# TPCapTH.net
KiCad netlist of a schematic drawn in Altium Designer
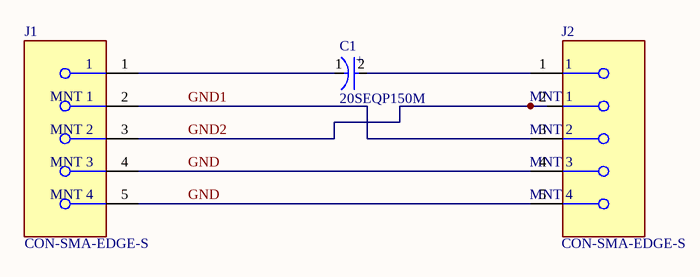
[diagram p0: TPCapTH.SchDoc]

(export (version "E")
  (design (tool "Eeschema 10.0.6"))
  (components
    (comp (ref "C1")
      (value "20SEQP150M")
      (footprint "FP-OS-CON-TH-F13-d_0_6-MFG")
      (description "Conductive Polymer Aluminum Solid Capacitors (OS-CON) 150uF ±20% 20V RADIAL TH 10x13mm")
      (fields (field (name "TOLERANCE") "20%"))
      (libsource (lib "Altium Content Vault") (part "203bc49f2ac43e59fd269a8c329ed05"))
    )
    (comp (ref "J1")
      (value "CON-SMA-EDGE-S")
      (footprint "FP-CON-SMA-EDGE-S-MFG")
      (description "CONN SMA JACK STR EDGE MNT")
      (fields
        (field (name "OCTOPART") "https://octopart.com/con-sma-edge-s-rf+solutions-70967450")
        (field (name "MANUFACTURER") "RF Solutions Ltd.")
      )
      (libsource (lib "") (part "a163d97a771fcdd2fd1f1a9264c171f_1"))
    )
    (comp (ref "J2")
      (value "CON-SMA-EDGE-S")
      (footprint "FP-CON-SMA-EDGE-S-MFG")
      (description "CONN SMA JACK STR EDGE MNT")
      (fields
        (field (name "OCTOPART") "https://octopart.com/con-sma-edge-s-rf+solutions-70967450")
        (field (name "MANUFACTURER") "RF Solutions Ltd.")
      )
      (libsource (lib "Altium Content Vault") (part "a163d97a771fcdd2fd1f1a9264c171f"))
    )
  )
  (nets
    (net (code "1") (name "/GND") (class "Default")
      (node (ref "J1") (pin "4") (pinfunction "MNT_3_4") (pintype "passive"))
      (node (ref "J1") (pin "5") (pinfunction "MNT_4_5") (pintype "passive"))
      (node (ref "J2") (pin "4") (pinfunction "MNT_3_4") (pintype "passive"))
      (node (ref "J2") (pin "5") (pinfunction "MNT_4_5") (pintype "passive"))
    )
    (net (code "2") (name "/GND1") (class "Default")
      (node (ref "J1") (pin "2") (pinfunction "MNT_1_2") (pintype "passive"))
      (node (ref "J2") (pin "3") (pinfunction "MNT_2_3") (pintype "passive"))
    )
    (net (code "3") (name "/GND2") (class "Default")
      (node (ref "J1") (pin "3") (pinfunction "MNT_2_3") (pintype "passive"))
      (node (ref "J2") (pin "2") (pinfunction "MNT_1_2") (pintype "passive"))
    )
    (net (code "4") (name "Net-(C1-A)") (class "Default")
      (node (ref "C1") (pin "2") (pinfunction "A_2") (pintype "passive"))
      (node (ref "J2") (pin "1") (pinfunction "1_1") (pintype "passive"))
    )
    (net (code "5") (name "Net-(C1-C)") (class "Default")
      (node (ref "C1") (pin "1") (pinfunction "C_1") (pintype "passive"))
      (node (ref "J1") (pin "1") (pinfunction "1_1") (pintype "passive"))
    )
  )
)
